# FPGA-OSC-JTAG.net
KiCad netlist of a schematic drawn in Altium Designer
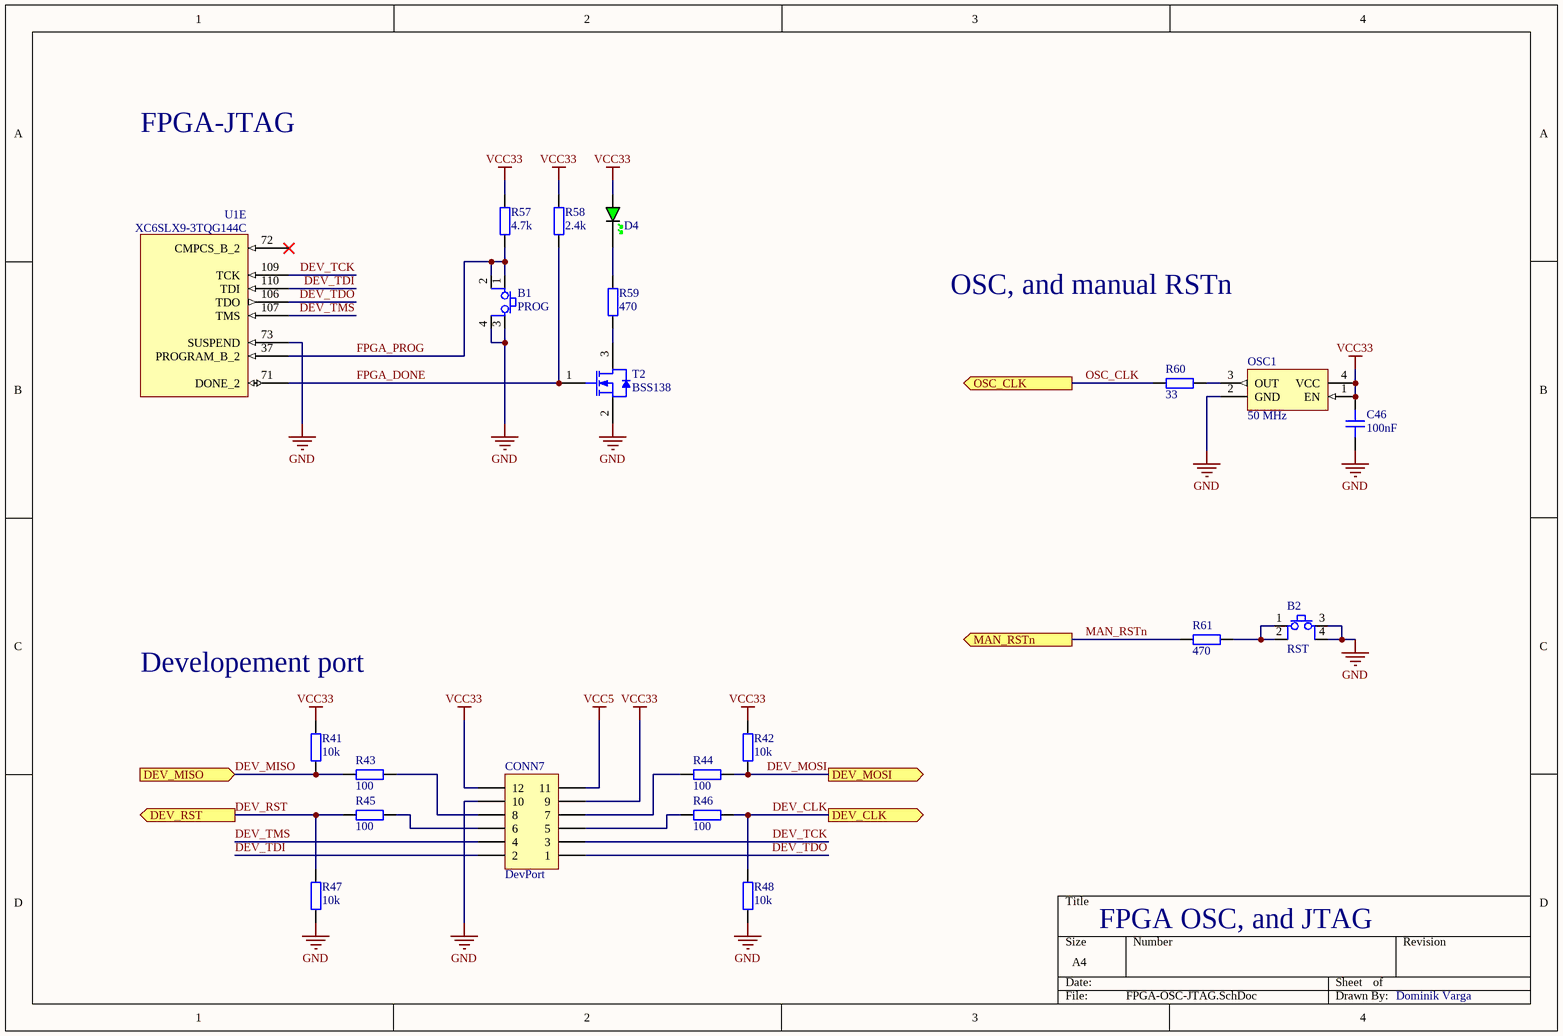
[diagram p0: FPGA-OSC-JTAG.SchDoc]

(export (version "E")
  (design (tool "Eeschema 10.0.6"))
  (components
    (comp (ref "B1")
      (value "PROG")
      (footprint "SMD_Button")
      (description "Basic SMD button")
      (fields
        (field (name "MANUFACTURER PART NUMBER") "TS-1109S-C-A")
        (field (name "MANUFACTURER") "XKB Connectivity")
      )
      (libsource (lib "NES-Components") (part "TS-1109S-C-A"))
    )
    (comp (ref "B2")
      (value "RST")
      (footprint "SMD_Button")
      (description "Basic SMD button")
      (fields
        (field (name "MANUFACTURER PART NUMBER") "TS-1109S-C-A")
        (field (name "MANUFACTURER") "XKB Connectivity")
      )
      (libsource (lib "NES-Components") (part "TS-1109S-C-A"))
    )
    (comp (ref "C46")
      (value "100nF")
      (footprint "CAP_SMD0603")
      (description "Capacitor SMD 0603")
      (libsource (lib "NES-Components") (part "CAP_0603"))
    )
    (comp (ref "CONN7")
      (value "DevPort")
      (footprint "HDR2X6")
      (description "Header, 6-Pin, Dual row")
      (fields (field (name "PUBLISHER") "Altium Limited"))
      (libsource (lib "NES-Components") (part "DevPort"))
    )
    (comp (ref "D4")
      (value "GREEN")
      (footprint "LED_G_SMD0603")
      (description "LED 0603 GREEN SMD")
      (libsource (lib "NES-Components") (part "LED_0603_GREEN"))
    )
    (comp (ref "OSC1")
      (value "50 MHz")
      (footprint "OSCSC508P500X700X200-4N")
      (libsource (lib "NES-Components") (part "50 MHz"))
    )
    (comp (ref "R41")
      (value "10k")
      (footprint "RES_SMD0603")
      (description "Resistor SMD 0603")
      (libsource (lib "NES-Components") (part "RES_0603"))
    )
    (comp (ref "R42")
      (value "10k")
      (footprint "RES_SMD0603")
      (description "Resistor SMD 0603")
      (libsource (lib "NES-Components") (part "RES_0603"))
    )
    (comp (ref "R43")
      (value "100")
      (footprint "RES_SMD0603")
      (description "Resistor SMD 0603")
      (libsource (lib "NES-Components") (part "RES_0603"))
    )
    (comp (ref "R44")
      (value "100")
      (footprint "RES_SMD0603")
      (description "Resistor SMD 0603")
      (libsource (lib "NES-Components") (part "RES_0603"))
    )
    (comp (ref "R45")
      (value "100")
      (footprint "RES_SMD0603")
      (description "Resistor SMD 0603")
      (libsource (lib "NES-Components") (part "RES_0603"))
    )
    (comp (ref "R46")
      (value "100")
      (footprint "RES_SMD0603")
      (description "Resistor SMD 0603")
      (libsource (lib "NES-Components") (part "RES_0603"))
    )
    (comp (ref "R47")
      (value "10k")
      (footprint "RES_SMD0603")
      (description "Resistor SMD 0603")
      (libsource (lib "NES-Components") (part "RES_0603"))
    )
    (comp (ref "R48")
      (value "10k")
      (footprint "RES_SMD0603")
      (description "Resistor SMD 0603")
      (libsource (lib "NES-Components") (part "RES_0603"))
    )
    (comp (ref "R57")
      (value "4.7k")
      (footprint "RES_SMD0603")
      (description "Resistor SMD 0603")
      (libsource (lib "NES-Components") (part "RES_0603"))
    )
    (comp (ref "R58")
      (value "2.4k")
      (footprint "RES_SMD0603")
      (description "Resistor SMD 0603")
      (libsource (lib "NES-Components") (part "RES_0603"))
    )
    (comp (ref "R59")
      (value "470")
      (footprint "RES_SMD0603")
      (description "Resistor SMD 0603")
      (libsource (lib "NES-Components") (part "RES_0603"))
    )
    (comp (ref "R60")
      (value "33")
      (footprint "RES_SMD0603")
      (description "Resistor SMD 0603")
      (libsource (lib "NES-Components") (part "RES_0603"))
    )
    (comp (ref "R61")
      (value "470")
      (footprint "RES_SMD0603")
      (description "Resistor SMD 0603")
      (libsource (lib "NES-Components") (part "RES_0603"))
    )
    (comp (ref "T2")
      (value "BSS138")
      (footprint "SOT95P240X110-3N")
      (description "N-Channel Enhancement Mode Field-Effect Transistor")
      (fields (field (name "MANUFACTURER") "NXP Semiconductors") (field (name "PARTNUMBER") "SI2302DS,215"))
      (libsource (lib "NES-Components") (part "BSS138"))
    )
    (comp (ref "U1")
      (value "XC6SLX9-3TQG144C")
      (footprint "QFP50P2200X2200X160-144N")
      (libsource (lib "NES-Components") (part "XC6SLX9-3TQG144C"))
    )
  )
  (nets
    (net (code "1") (name "/DEV_CLK") (class "Default")
      (node (ref "R46") (pin "2") (pinfunction "2_2") (pintype "passive"))
      (node (ref "R48") (pin "1") (pinfunction "1_1") (pintype "passive"))
    )
    (net (code "2") (name "/DEV_MISO") (class "Default")
      (node (ref "R41") (pin "2") (pinfunction "2_2") (pintype "passive"))
      (node (ref "R43") (pin "1") (pinfunction "1_1") (pintype "passive"))
    )
    (net (code "3") (name "/DEV_MOSI") (class "Default")
      (node (ref "R42") (pin "2") (pinfunction "2_2") (pintype "passive"))
      (node (ref "R44") (pin "2") (pinfunction "2_2") (pintype "passive"))
    )
    (net (code "4") (name "/DEV_RST") (class "Default")
      (node (ref "R45") (pin "1") (pinfunction "1_1") (pintype "passive"))
      (node (ref "R47") (pin "1") (pinfunction "1_1") (pintype "passive"))
    )
    (net (code "5") (name "/DEV_TCK") (class "Default")
      (node (ref "CONN7") (pin "3") (pinfunction "3_3") (pintype "passive"))
      (node (ref "U1") (pin "109") (pinfunction "TCK_109") (pintype "input"))
    )
    (net (code "6") (name "/DEV_TDI") (class "Default")
      (node (ref "CONN7") (pin "2") (pinfunction "2_2") (pintype "passive"))
      (node (ref "U1") (pin "110") (pinfunction "TDI_110") (pintype "input"))
    )
    (net (code "7") (name "/DEV_TDO") (class "Default")
      (node (ref "CONN7") (pin "1") (pinfunction "1_1") (pintype "passive"))
      (node (ref "U1") (pin "106") (pinfunction "TDO_106") (pintype "output"))
    )
    (net (code "8") (name "/DEV_TMS") (class "Default")
      (node (ref "CONN7") (pin "4") (pinfunction "4_4") (pintype "passive"))
      (node (ref "U1") (pin "107") (pinfunction "TMS_107") (pintype "input"))
    )
    (net (code "9") (name "/FPGA_DONE") (class "Default")
      (node (ref "R58") (pin "1") (pinfunction "1_1") (pintype "passive"))
      (node (ref "T2") (pin "1") (pinfunction "G_1") (pintype "passive"))
      (node (ref "U1") (pin "71") (pinfunction "DONE_2_71") (pintype "bidirectional"))
    )
    (net (code "10") (name "/FPGA_PROG") (class "Default")
      (node (ref "B1") (pin "1") (pinfunction "1_1") (pintype "passive"))
      (node (ref "B1") (pin "2") (pinfunction "2_2") (pintype "passive"))
      (node (ref "R57") (pin "1") (pinfunction "1_1") (pintype "passive"))
      (node (ref "U1") (pin "37") (pinfunction "PROGRAM_B_2_37") (pintype "input"))
    )
    (net (code "11") (name "/MAN_RSTn") (class "Default")
      (node (ref "R61") (pin "2") (pinfunction "2_2") (pintype "passive"))
    )
    (net (code "12") (name "/OSC_CLK") (class "Default")
      (node (ref "R60") (pin "2") (pinfunction "2_2") (pintype "passive"))
    )
    (net (code "13") (name "GND") (class "Default")
      (node (ref "B1") (pin "3") (pinfunction "3_3") (pintype "passive"))
      (node (ref "B1") (pin "4") (pinfunction "4_4") (pintype "passive"))
      (node (ref "B2") (pin "3") (pinfunction "3_3") (pintype "passive"))
      (node (ref "B2") (pin "4") (pinfunction "4_4") (pintype "passive"))
      (node (ref "C46") (pin "1") (pinfunction "1_1") (pintype "passive"))
      (node (ref "CONN7") (pin "10") (pinfunction "10_10") (pintype "passive"))
      (node (ref "OSC1") (pin "2") (pinfunction "GND_2") (pintype "passive"))
      (node (ref "R47") (pin "2") (pinfunction "2_2") (pintype "passive"))
      (node (ref "R48") (pin "2") (pinfunction "2_2") (pintype "passive"))
      (node (ref "T2") (pin "2") (pinfunction "S_2") (pintype "passive"))
      (node (ref "U1") (pin "73") (pinfunction "SUSPEND_73") (pintype "input"))
    )
    (net (code "14") (name "Net-(B2-Pad1)") (class "Default")
      (node (ref "B2") (pin "1") (pinfunction "1_1") (pintype "passive"))
      (node (ref "B2") (pin "2") (pinfunction "2_2") (pintype "passive"))
      (node (ref "R61") (pin "1") (pinfunction "1_1") (pintype "passive"))
    )
    (net (code "15") (name "Net-(CONN7-Pad5)") (class "Default")
      (node (ref "CONN7") (pin "5") (pinfunction "5_5") (pintype "passive"))
      (node (ref "R46") (pin "1") (pinfunction "1_1") (pintype "passive"))
    )
    (net (code "16") (name "Net-(CONN7-Pad6)") (class "Default")
      (node (ref "CONN7") (pin "6") (pinfunction "6_6") (pintype "passive"))
      (node (ref "R45") (pin "2") (pinfunction "2_2") (pintype "passive"))
    )
    (net (code "17") (name "Net-(CONN7-Pad7)") (class "Default")
      (node (ref "CONN7") (pin "7") (pinfunction "7_7") (pintype "passive"))
      (node (ref "R44") (pin "1") (pinfunction "1_1") (pintype "passive"))
    )
    (net (code "18") (name "Net-(CONN7-Pad8)") (class "Default")
      (node (ref "CONN7") (pin "8") (pinfunction "8_8") (pintype "passive"))
      (node (ref "R43") (pin "2") (pinfunction "2_2") (pintype "passive"))
    )
    (net (code "19") (name "Net-(D4-K)") (class "Default")
      (node (ref "D4") (pin "2") (pinfunction "K_2") (pintype "passive"))
      (node (ref "R59") (pin "2") (pinfunction "2_2") (pintype "passive"))
    )
    (net (code "20") (name "Net-(OSC1-OUT)") (class "Default")
      (node (ref "OSC1") (pin "3") (pinfunction "OUT_3") (pintype "output"))
      (node (ref "R60") (pin "1") (pinfunction "1_1") (pintype "passive"))
    )
    (net (code "21") (name "Net-(T2-D)") (class "Default")
      (node (ref "R59") (pin "1") (pinfunction "1_1") (pintype "passive"))
      (node (ref "T2") (pin "3") (pinfunction "D_3") (pintype "passive"))
    )
    (net (code "22") (name "VCC5") (class "Default")
      (node (ref "CONN7") (pin "11") (pinfunction "11_11") (pintype "passive"))
    )
    (net (code "23") (name "VCC33") (class "Default")
      (node (ref "C46") (pin "2") (pinfunction "2_2") (pintype "passive"))
      (node (ref "CONN7") (pin "12") (pinfunction "12_12") (pintype "passive"))
      (node (ref "CONN7") (pin "9") (pinfunction "9_9") (pintype "passive"))
      (node (ref "D4") (pin "1") (pinfunction "A_1") (pintype "passive"))
      (node (ref "OSC1") (pin "1") (pinfunction "EN_1") (pintype "input"))
      (node (ref "OSC1") (pin "4") (pinfunction "VCC_4") (pintype "passive"))
      (node (ref "R41") (pin "1") (pinfunction "1_1") (pintype "passive"))
      (node (ref "R42") (pin "1") (pinfunction "1_1") (pintype "passive"))
      (node (ref "R57") (pin "2") (pinfunction "2_2") (pintype "passive"))
      (node (ref "R58") (pin "2") (pinfunction "2_2") (pintype "passive"))
    )
    (net (code "24") (name "unconnected-(U1E-CMPCS_B_2-Pad72)") (class "Default")
      (node (ref "U1") (pin "72") (pinfunction "CMPCS_B_2_72") (pintype "input+no_connect"))
    )
  )
)
